# USB.net
KiCad netlist of a schematic drawn in Altium Designer
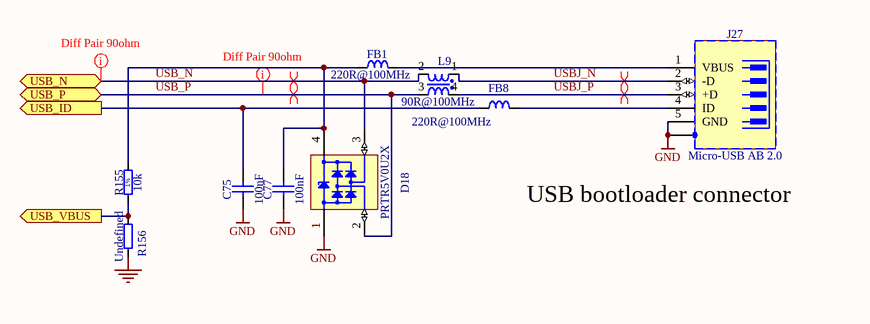
[diagram p0: USB.SchDoc]

(export (version "E")
  (design (tool "Eeschema 10.0.6"))
  (components
    (comp (ref "C75")
      (value "100nF")
      (footprint "CAPC1005X55N")
      (description "Non-polarised capacitor")
      (fields
        (field (name "PART NUMBER") "CC0402_100NF_16V_10%_X7R")
        (field (name "VOLTAGE") "16V")
        (field (name "AUTHOR") "CERN DEM JLC")
      )
      (libsource (lib "Capacitors") (part "Capacitor - non polarized"))
    )
    (comp (ref "C77")
      (value "100nF")
      (footprint "CAPC1005X55N")
      (description "Non-polarised capacitor")
      (fields
        (field (name "PART NUMBER") "CC0402_100NF_16V_10%_X7R")
        (field (name "VOLTAGE") "16V")
        (field (name "AUTHOR") "CERN DEM JLC")
      )
      (libsource (lib "Capacitors") (part "Capacitor - non polarized"))
    )
    (comp (ref "D18")
      (value "PRTR5V0U2X")
      (footprint "SOT190P230X110-4N")
      (description "Ultra Low Capacitance Double Rail-to-Rail ESD Protection Diode")
      (fields
        (field (name "VOLTAGE") "5.5V")
        (field (name "MANUFACTURER") "NXP SEMICONDUCTORS")
        (field (name "AUTHOR") "CERN DEM JLC")
      )
      (libsource (lib "ICs And Semiconductors") (part "PRTR5V0U2X"))
    )
    (comp (ref "FB1")
      (value "220R@100MHz")
      (footprint "INDC2012X105N")
      (description "Inductor")
      (fields
        (field (name "PART NUMBER") "IND0805_MURATA_BLM21PG221SN1D")
        (field (name "POWER") "2A")
        (field (name "AUTHOR") "CERN DEM JLC")
      )
      (libsource (lib "Inductors & Transformers") (part "Inductor"))
    )
    (comp (ref "FB8")
      (value "220R@100MHz")
      (footprint "INDC2012X105N")
      (description "Inductor")
      (fields
        (field (name "PART NUMBER") "IND0805_MURATA_BLM21PG221SN1D")
        (field (name "POWER") "2A")
        (field (name "AUTHOR") "CERN DEM JLC")
      )
      (libsource (lib "Inductors & Transformers") (part "Inductor"))
    )
    (comp (ref "J27")
      (value "Micro-USB AB 2.0")
      (footprint "HIROSE_ZX62RD-AB-5P8(30)")
      (description "5 Pin + 1 Shield USB Receptacle")
      (fields
        (field (name "PART NUMBER") "HIROSE_ZX62RD-AB-5P8(30)")
        (field (name "MANUFACTURER") "HIROSE (HRS)")
        (field (name "AUTHOR") "CERN DEM JMW")
      )
      (libsource (lib "Connectors") (part "Connector USB 5 Pin + 1Shield"))
    )
    (comp (ref "L9")
      (value "90R@100MHz")
      (footprint "IND_MURATA_DLW21S")
      (description "Inductor Common Mode")
      (fields
        (field (name "PART NUMBER") "IND_MURATA_DLW21SN900SQ2L")
        (field (name "POWER") "330mA")
        (field (name "AUTHOR") "CERN DEM JLC")
      )
      (libsource (lib "Inductors & Transformers") (part "Inductor Common Mode 1Dot-2 4Dot-3"))
    )
    (comp (ref "R155")
      (value "10k")
      (footprint "RESC1608X55N")
      (description "Resistor - 1%")
      (fields
        (field (name "PART NUMBER") "R0603_10K_1%_0.1W_100PPM")
        (field (name "POWER") "0.1W")
        (field (name "AUTHOR") "CERN DEM JLC")
      )
      (libsource (lib "Resistors") (part "Resistor - 1%"))
    )
    (comp (ref "R156")
      (value "Undefined")
      (footprint "RESC1005X40N")
      (description "Resistor")
      (fields (field (name "PART NUMBER") "R0402_NO-VALUE") (field (name "AUTHOR") "CERN DEM JLC"))
      (libsource (lib "Resistors") (part "Resistor"))
    )
  )
  (nets
    (net (code "1") (name "/USBJ_N") (class "Default")
      (node (ref "J27") (pin "2") (pinfunction "-D_2") (pintype "bidirectional"))
      (node (ref "L9") (pin "1") (pinfunction "1_1") (pintype "passive"))
    )
    (net (code "2") (name "/USBJ_P") (class "Default")
      (node (ref "J27") (pin "3") (pinfunction "+D_3") (pintype "bidirectional"))
      (node (ref "L9") (pin "4") (pinfunction "4_4") (pintype "passive"))
    )
    (net (code "3") (name "/USB_ID") (class "Default")
      (node (ref "C75") (pin "2") (pinfunction "2_2") (pintype "passive"))
      (node (ref "FB8") (pin "1") (pinfunction "1_1") (pintype "passive"))
    )
    (net (code "4") (name "/USB_N") (class "Default")
      (node (ref "D18") (pin "3") (pinfunction "I/O2_3") (pintype "bidirectional"))
      (node (ref "L9") (pin "2") (pinfunction "2_2") (pintype "passive"))
    )
    (net (code "5") (name "/USB_P") (class "Default")
      (node (ref "D18") (pin "2") (pinfunction "I/O1_2") (pintype "bidirectional"))
      (node (ref "L9") (pin "3") (pinfunction "3_3") (pintype "passive"))
    )
    (net (code "6") (name "/USB_VBUS") (class "Default")
      (node (ref "R155") (pin "1") (pinfunction "1_1") (pintype "passive"))
      (node (ref "R156") (pin "1") (pinfunction "1_1") (pintype "passive"))
    )
    (net (code "7") (name "GND") (class "Default")
      (node (ref "C75") (pin "1") (pinfunction "1_1") (pintype "passive"))
      (node (ref "C77") (pin "1") (pinfunction "1_1") (pintype "passive"))
      (node (ref "D18") (pin "1") (pinfunction "GND_1") (pintype "power_in"))
      (node (ref "J27") (pin "5") (pinfunction "GND_5") (pintype "power_in"))
      (node (ref "J27") (pin "6") (pinfunction "SH_6") (pintype "power_in"))
      (node (ref "R156") (pin "2") (pinfunction "2_2") (pintype "passive"))
    )
    (net (code "8") (name "Net-(D18-VCC)") (class "Default")
      (node (ref "C77") (pin "2") (pinfunction "2_2") (pintype "passive"))
      (node (ref "D18") (pin "4") (pinfunction "VCC_4") (pintype "power_in"))
      (node (ref "FB1") (pin "1") (pinfunction "1_1") (pintype "passive"))
      (node (ref "R155") (pin "2") (pinfunction "2_2") (pintype "passive"))
    )
    (net (code "9") (name "Net-(J27-ID)") (class "Default")
      (node (ref "FB8") (pin "2") (pinfunction "2_2") (pintype "passive"))
      (node (ref "J27") (pin "4") (pinfunction "ID_4") (pintype "passive"))
    )
    (net (code "10") (name "Net-(J27-VBUS)") (class "Default")
      (node (ref "FB1") (pin "2") (pinfunction "2_2") (pintype "passive"))
      (node (ref "J27") (pin "1") (pinfunction "VBUS_1") (pintype "power_in"))
    )
  )
)
